# LED_Matrix-2.net
KiCad netlist of a schematic drawn in Altium Designer
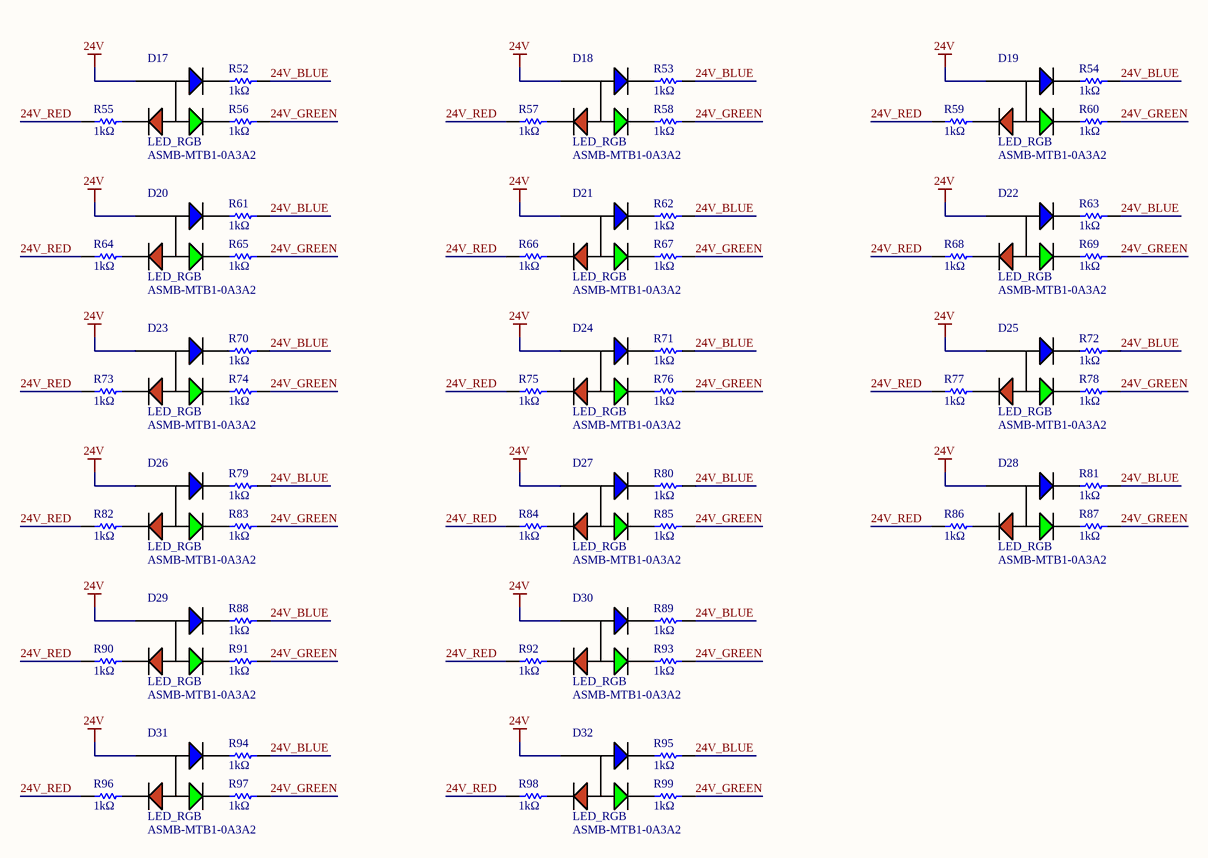
[diagram p0: LED Matrix-2.SchDoc]

(export (version "E")
  (design (tool "Eeschema 10.0.6"))
  (components
    (comp (ref "D17")
      (value "LED_RGB")
      (footprint "LED_RGB")
      (description "LED RGB DIFFUSED 4PLCC SMD")
      (fields (field (name "MANUFACTURER PART NUMBER 1") "ASMB-MTB1-0A3A2"))
      (libsource (lib "UWRT_Schematic_Library_2020") (part "LED_RGB"))
    )
    (comp (ref "D18")
      (value "LED_RGB")
      (footprint "LED_RGB")
      (description "LED RGB DIFFUSED 4PLCC SMD")
      (fields (field (name "MANUFACTURER PART NUMBER 1") "ASMB-MTB1-0A3A2"))
      (libsource (lib "UWRT_Schematic_Library_2020") (part "LED_RGB"))
    )
    (comp (ref "D19")
      (value "LED_RGB")
      (footprint "LED_RGB")
      (description "LED RGB DIFFUSED 4PLCC SMD")
      (fields (field (name "MANUFACTURER PART NUMBER 1") "ASMB-MTB1-0A3A2"))
      (libsource (lib "UWRT_Schematic_Library_2020") (part "LED_RGB"))
    )
    (comp (ref "D20")
      (value "LED_RGB")
      (footprint "LED_RGB")
      (description "LED RGB DIFFUSED 4PLCC SMD")
      (fields (field (name "MANUFACTURER PART NUMBER 1") "ASMB-MTB1-0A3A2"))
      (libsource (lib "UWRT_Schematic_Library_2020") (part "LED_RGB"))
    )
    (comp (ref "D21")
      (value "LED_RGB")
      (footprint "LED_RGB")
      (description "LED RGB DIFFUSED 4PLCC SMD")
      (fields (field (name "MANUFACTURER PART NUMBER 1") "ASMB-MTB1-0A3A2"))
      (libsource (lib "UWRT_Schematic_Library_2020") (part "LED_RGB"))
    )
    (comp (ref "D22")
      (value "LED_RGB")
      (footprint "LED_RGB")
      (description "LED RGB DIFFUSED 4PLCC SMD")
      (fields (field (name "MANUFACTURER PART NUMBER 1") "ASMB-MTB1-0A3A2"))
      (libsource (lib "UWRT_Schematic_Library_2020") (part "LED_RGB"))
    )
    (comp (ref "D23")
      (value "LED_RGB")
      (footprint "LED_RGB")
      (description "LED RGB DIFFUSED 4PLCC SMD")
      (fields (field (name "MANUFACTURER PART NUMBER 1") "ASMB-MTB1-0A3A2"))
      (libsource (lib "UWRT_Schematic_Library_2020") (part "LED_RGB"))
    )
    (comp (ref "D24")
      (value "LED_RGB")
      (footprint "LED_RGB")
      (description "LED RGB DIFFUSED 4PLCC SMD")
      (fields (field (name "MANUFACTURER PART NUMBER 1") "ASMB-MTB1-0A3A2"))
      (libsource (lib "UWRT_Schematic_Library_2020") (part "LED_RGB"))
    )
    (comp (ref "D25")
      (value "LED_RGB")
      (footprint "LED_RGB")
      (description "LED RGB DIFFUSED 4PLCC SMD")
      (fields (field (name "MANUFACTURER PART NUMBER 1") "ASMB-MTB1-0A3A2"))
      (libsource (lib "UWRT_Schematic_Library_2020") (part "LED_RGB"))
    )
    (comp (ref "D26")
      (value "LED_RGB")
      (footprint "LED_RGB")
      (description "LED RGB DIFFUSED 4PLCC SMD")
      (fields (field (name "MANUFACTURER PART NUMBER 1") "ASMB-MTB1-0A3A2"))
      (libsource (lib "UWRT_Schematic_Library_2020") (part "LED_RGB"))
    )
    (comp (ref "D27")
      (value "LED_RGB")
      (footprint "LED_RGB")
      (description "LED RGB DIFFUSED 4PLCC SMD")
      (fields (field (name "MANUFACTURER PART NUMBER 1") "ASMB-MTB1-0A3A2"))
      (libsource (lib "UWRT_Schematic_Library_2020") (part "LED_RGB"))
    )
    (comp (ref "D28")
      (value "LED_RGB")
      (footprint "LED_RGB")
      (description "LED RGB DIFFUSED 4PLCC SMD")
      (fields (field (name "MANUFACTURER PART NUMBER 1") "ASMB-MTB1-0A3A2"))
      (libsource (lib "UWRT_Schematic_Library_2020") (part "LED_RGB"))
    )
    (comp (ref "D29")
      (value "LED_RGB")
      (footprint "LED_RGB")
      (description "LED RGB DIFFUSED 4PLCC SMD")
      (fields (field (name "MANUFACTURER PART NUMBER 1") "ASMB-MTB1-0A3A2"))
      (libsource (lib "UWRT_Schematic_Library_2020") (part "LED_RGB"))
    )
    (comp (ref "D30")
      (value "LED_RGB")
      (footprint "LED_RGB")
      (description "LED RGB DIFFUSED 4PLCC SMD")
      (fields (field (name "MANUFACTURER PART NUMBER 1") "ASMB-MTB1-0A3A2"))
      (libsource (lib "UWRT_Schematic_Library_2020") (part "LED_RGB"))
    )
    (comp (ref "D31")
      (value "LED_RGB")
      (footprint "LED_RGB")
      (description "LED RGB DIFFUSED 4PLCC SMD")
      (fields (field (name "MANUFACTURER PART NUMBER 1") "ASMB-MTB1-0A3A2"))
      (libsource (lib "UWRT_Schematic_Library_2020") (part "LED_RGB"))
    )
    (comp (ref "D32")
      (value "LED_RGB")
      (footprint "LED_RGB")
      (description "LED RGB DIFFUSED 4PLCC SMD")
      (fields (field (name "MANUFACTURER PART NUMBER 1") "ASMB-MTB1-0A3A2"))
      (libsource (lib "UWRT_Schematic_Library_2020") (part "LED_RGB"))
    )
    (comp (ref "R52")
      (value "1kΩ")
      (footprint "RESC2012X60N")
      (description "RES SMD 1K OHM 1% 1/8W 0805")
      (fields (field (name "TOLERANCE") "1%"))
      (libsource (lib "UWRT_Schematic_Library_2020") (part "RES_1kΩ_0805"))
    )
    (comp (ref "R53")
      (value "1kΩ")
      (footprint "RESC2012X60N")
      (description "RES SMD 1K OHM 1% 1/8W 0805")
      (fields (field (name "TOLERANCE") "1%"))
      (libsource (lib "UWRT_Schematic_Library_2020") (part "RES_1kΩ_0805"))
    )
    (comp (ref "R54")
      (value "1kΩ")
      (footprint "RESC2012X60N")
      (description "RES SMD 1K OHM 1% 1/8W 0805")
      (fields (field (name "TOLERANCE") "1%"))
      (libsource (lib "UWRT_Schematic_Library_2020") (part "RES_1kΩ_0805"))
    )
    (comp (ref "R55")
      (value "1kΩ")
      (footprint "RESC2012X60N")
      (description "RES SMD 1K OHM 1% 1/8W 0805")
      (fields (field (name "TOLERANCE") "1%"))
      (libsource (lib "UWRT_Schematic_Library_2020") (part "RES_1kΩ_0805"))
    )
    (comp (ref "R56")
      (value "1kΩ")
      (footprint "RESC2012X60N")
      (description "RES SMD 1K OHM 1% 1/8W 0805")
      (fields (field (name "TOLERANCE") "1%"))
      (libsource (lib "UWRT_Schematic_Library_2020") (part "RES_1kΩ_0805"))
    )
    (comp (ref "R57")
      (value "1kΩ")
      (footprint "RESC2012X60N")
      (description "RES SMD 1K OHM 1% 1/8W 0805")
      (fields (field (name "TOLERANCE") "1%"))
      (libsource (lib "UWRT_Schematic_Library_2020") (part "RES_1kΩ_0805"))
    )
    (comp (ref "R58")
      (value "1kΩ")
      (footprint "RESC2012X60N")
      (description "RES SMD 1K OHM 1% 1/8W 0805")
      (fields (field (name "TOLERANCE") "1%"))
      (libsource (lib "UWRT_Schematic_Library_2020") (part "RES_1kΩ_0805"))
    )
    (comp (ref "R59")
      (value "1kΩ")
      (footprint "RESC2012X60N")
      (description "RES SMD 1K OHM 1% 1/8W 0805")
      (fields (field (name "TOLERANCE") "1%"))
      (libsource (lib "UWRT_Schematic_Library_2020") (part "RES_1kΩ_0805"))
    )
    (comp (ref "R60")
      (value "1kΩ")
      (footprint "RESC2012X60N")
      (description "RES SMD 1K OHM 1% 1/8W 0805")
      (fields (field (name "TOLERANCE") "1%"))
      (libsource (lib "UWRT_Schematic_Library_2020") (part "RES_1kΩ_0805"))
    )
    (comp (ref "R61")
      (value "1kΩ")
      (footprint "RESC2012X60N")
      (description "RES SMD 1K OHM 1% 1/8W 0805")
      (fields (field (name "TOLERANCE") "1%"))
      (libsource (lib "UWRT_Schematic_Library_2020") (part "RES_1kΩ_0805"))
    )
    (comp (ref "R62")
      (value "1kΩ")
      (footprint "RESC2012X60N")
      (description "RES SMD 1K OHM 1% 1/8W 0805")
      (fields (field (name "TOLERANCE") "1%"))
      (libsource (lib "UWRT_Schematic_Library_2020") (part "RES_1kΩ_0805"))
    )
    (comp (ref "R63")
      (value "1kΩ")
      (footprint "RESC2012X60N")
      (description "RES SMD 1K OHM 1% 1/8W 0805")
      (fields (field (name "TOLERANCE") "1%"))
      (libsource (lib "UWRT_Schematic_Library_2020") (part "RES_1kΩ_0805"))
    )
    (comp (ref "R64")
      (value "1kΩ")
      (footprint "RESC2012X60N")
      (description "RES SMD 1K OHM 1% 1/8W 0805")
      (fields (field (name "TOLERANCE") "1%"))
      (libsource (lib "UWRT_Schematic_Library_2020") (part "RES_1kΩ_0805"))
    )
    (comp (ref "R65")
      (value "1kΩ")
      (footprint "RESC2012X60N")
      (description "RES SMD 1K OHM 1% 1/8W 0805")
      (fields (field (name "TOLERANCE") "1%"))
      (libsource (lib "UWRT_Schematic_Library_2020") (part "RES_1kΩ_0805"))
    )
    (comp (ref "R66")
      (value "1kΩ")
      (footprint "RESC2012X60N")
      (description "RES SMD 1K OHM 1% 1/8W 0805")
      (fields (field (name "TOLERANCE") "1%"))
      (libsource (lib "UWRT_Schematic_Library_2020") (part "RES_1kΩ_0805"))
    )
    (comp (ref "R67")
      (value "1kΩ")
      (footprint "RESC2012X60N")
      (description "RES SMD 1K OHM 1% 1/8W 0805")
      (fields (field (name "TOLERANCE") "1%"))
      (libsource (lib "UWRT_Schematic_Library_2020") (part "RES_1kΩ_0805"))
    )
    (comp (ref "R68")
      (value "1kΩ")
      (footprint "RESC2012X60N")
      (description "RES SMD 1K OHM 1% 1/8W 0805")
      (fields (field (name "TOLERANCE") "1%"))
      (libsource (lib "UWRT_Schematic_Library_2020") (part "RES_1kΩ_0805"))
    )
    (comp (ref "R69")
      (value "1kΩ")
      (footprint "RESC2012X60N")
      (description "RES SMD 1K OHM 1% 1/8W 0805")
      (fields (field (name "TOLERANCE") "1%"))
      (libsource (lib "UWRT_Schematic_Library_2020") (part "RES_1kΩ_0805"))
    )
    (comp (ref "R70")
      (value "1kΩ")
      (footprint "RESC2012X60N")
      (description "RES SMD 1K OHM 1% 1/8W 0805")
      (fields (field (name "TOLERANCE") "1%"))
      (libsource (lib "UWRT_Schematic_Library_2020") (part "RES_1kΩ_0805"))
    )
    (comp (ref "R71")
      (value "1kΩ")
      (footprint "RESC2012X60N")
      (description "RES SMD 1K OHM 1% 1/8W 0805")
      (fields (field (name "TOLERANCE") "1%"))
      (libsource (lib "UWRT_Schematic_Library_2020") (part "RES_1kΩ_0805"))
    )
    (comp (ref "R72")
      (value "1kΩ")
      (footprint "RESC2012X60N")
      (description "RES SMD 1K OHM 1% 1/8W 0805")
      (fields (field (name "TOLERANCE") "1%"))
      (libsource (lib "UWRT_Schematic_Library_2020") (part "RES_1kΩ_0805"))
    )
    (comp (ref "R73")
      (value "1kΩ")
      (footprint "RESC2012X60N")
      (description "RES SMD 1K OHM 1% 1/8W 0805")
      (fields (field (name "TOLERANCE") "1%"))
      (libsource (lib "UWRT_Schematic_Library_2020") (part "RES_1kΩ_0805"))
    )
    (comp (ref "R74")
      (value "1kΩ")
      (footprint "RESC2012X60N")
      (description "RES SMD 1K OHM 1% 1/8W 0805")
      (fields (field (name "TOLERANCE") "1%"))
      (libsource (lib "UWRT_Schematic_Library_2020") (part "RES_1kΩ_0805"))
    )
    (comp (ref "R75")
      (value "1kΩ")
      (footprint "RESC2012X60N")
      (description "RES SMD 1K OHM 1% 1/8W 0805")
      (fields (field (name "TOLERANCE") "1%"))
      (libsource (lib "UWRT_Schematic_Library_2020") (part "RES_1kΩ_0805"))
    )
    (comp (ref "R76")
      (value "1kΩ")
      (footprint "RESC2012X60N")
      (description "RES SMD 1K OHM 1% 1/8W 0805")
      (fields (field (name "TOLERANCE") "1%"))
      (libsource (lib "UWRT_Schematic_Library_2020") (part "RES_1kΩ_0805"))
    )
    (comp (ref "R77")
      (value "1kΩ")
      (footprint "RESC2012X60N")
      (description "RES SMD 1K OHM 1% 1/8W 0805")
      (fields (field (name "TOLERANCE") "1%"))
      (libsource (lib "UWRT_Schematic_Library_2020") (part "RES_1kΩ_0805"))
    )
    (comp (ref "R78")
      (value "1kΩ")
      (footprint "RESC2012X60N")
      (description "RES SMD 1K OHM 1% 1/8W 0805")
      (fields (field (name "TOLERANCE") "1%"))
      (libsource (lib "UWRT_Schematic_Library_2020") (part "RES_1kΩ_0805"))
    )
    (comp (ref "R79")
      (value "1kΩ")
      (footprint "RESC2012X60N")
      (description "RES SMD 1K OHM 1% 1/8W 0805")
      (fields (field (name "TOLERANCE") "1%"))
      (libsource (lib "UWRT_Schematic_Library_2020") (part "RES_1kΩ_0805"))
    )
    (comp (ref "R80")
      (value "1kΩ")
      (footprint "RESC2012X60N")
      (description "RES SMD 1K OHM 1% 1/8W 0805")
      (fields (field (name "TOLERANCE") "1%"))
      (libsource (lib "UWRT_Schematic_Library_2020") (part "RES_1kΩ_0805"))
    )
    (comp (ref "R81")
      (value "1kΩ")
      (footprint "RESC2012X60N")
      (description "RES SMD 1K OHM 1% 1/8W 0805")
      (fields (field (name "TOLERANCE") "1%"))
      (libsource (lib "UWRT_Schematic_Library_2020") (part "RES_1kΩ_0805"))
    )
    (comp (ref "R82")
      (value "1kΩ")
      (footprint "RESC2012X60N")
      (description "RES SMD 1K OHM 1% 1/8W 0805")
      (fields (field (name "TOLERANCE") "1%"))
      (libsource (lib "UWRT_Schematic_Library_2020") (part "RES_1kΩ_0805"))
    )
    (comp (ref "R83")
      (value "1kΩ")
      (footprint "RESC2012X60N")
      (description "RES SMD 1K OHM 1% 1/8W 0805")
      (fields (field (name "TOLERANCE") "1%"))
      (libsource (lib "UWRT_Schematic_Library_2020") (part "RES_1kΩ_0805"))
    )
    (comp (ref "R84")
      (value "1kΩ")
      (footprint "RESC2012X60N")
      (description "RES SMD 1K OHM 1% 1/8W 0805")
      (fields (field (name "TOLERANCE") "1%"))
      (libsource (lib "UWRT_Schematic_Library_2020") (part "RES_1kΩ_0805"))
    )
    (comp (ref "R85")
      (value "1kΩ")
      (footprint "RESC2012X60N")
      (description "RES SMD 1K OHM 1% 1/8W 0805")
      (fields (field (name "TOLERANCE") "1%"))
      (libsource (lib "UWRT_Schematic_Library_2020") (part "RES_1kΩ_0805"))
    )
    (comp (ref "R86")
      (value "1kΩ")
      (footprint "RESC2012X60N")
      (description "RES SMD 1K OHM 1% 1/8W 0805")
      (fields (field (name "TOLERANCE") "1%"))
      (libsource (lib "UWRT_Schematic_Library_2020") (part "RES_1kΩ_0805"))
    )
    (comp (ref "R87")
      (value "1kΩ")
      (footprint "RESC2012X60N")
      (description "RES SMD 1K OHM 1% 1/8W 0805")
      (fields (field (name "TOLERANCE") "1%"))
      (libsource (lib "UWRT_Schematic_Library_2020") (part "RES_1kΩ_0805"))
    )
    (comp (ref "R88")
      (value "1kΩ")
      (footprint "RESC2012X60N")
      (description "RES SMD 1K OHM 1% 1/8W 0805")
      (fields (field (name "TOLERANCE") "1%"))
      (libsource (lib "UWRT_Schematic_Library_2020") (part "RES_1kΩ_0805"))
    )
    (comp (ref "R89")
      (value "1kΩ")
      (footprint "RESC2012X60N")
      (description "RES SMD 1K OHM 1% 1/8W 0805")
      (fields (field (name "TOLERANCE") "1%"))
      (libsource (lib "UWRT_Schematic_Library_2020") (part "RES_1kΩ_0805"))
    )
    (comp (ref "R90")
      (value "1kΩ")
      (footprint "RESC2012X60N")
      (description "RES SMD 1K OHM 1% 1/8W 0805")
      (fields (field (name "TOLERANCE") "1%"))
      (libsource (lib "UWRT_Schematic_Library_2020") (part "RES_1kΩ_0805"))
    )
    (comp (ref "R91")
      (value "1kΩ")
      (footprint "RESC2012X60N")
      (description "RES SMD 1K OHM 1% 1/8W 0805")
      (fields (field (name "TOLERANCE") "1%"))
      (libsource (lib "UWRT_Schematic_Library_2020") (part "RES_1kΩ_0805"))
    )
    (comp (ref "R92")
      (value "1kΩ")
      (footprint "RESC2012X60N")
      (description "RES SMD 1K OHM 1% 1/8W 0805")
      (fields (field (name "TOLERANCE") "1%"))
      (libsource (lib "UWRT_Schematic_Library_2020") (part "RES_1kΩ_0805"))
    )
    (comp (ref "R93")
      (value "1kΩ")
      (footprint "RESC2012X60N")
      (description "RES SMD 1K OHM 1% 1/8W 0805")
      (fields (field (name "TOLERANCE") "1%"))
      (libsource (lib "UWRT_Schematic_Library_2020") (part "RES_1kΩ_0805"))
    )
    (comp (ref "R94")
      (value "1kΩ")
      (footprint "RESC2012X60N")
      (description "RES SMD 1K OHM 1% 1/8W 0805")
      (fields (field (name "TOLERANCE") "1%"))
      (libsource (lib "UWRT_Schematic_Library_2020") (part "RES_1kΩ_0805"))
    )
    (comp (ref "R95")
      (value "1kΩ")
      (footprint "RESC2012X60N")
      (description "RES SMD 1K OHM 1% 1/8W 0805")
      (fields (field (name "TOLERANCE") "1%"))
      (libsource (lib "UWRT_Schematic_Library_2020") (part "RES_1kΩ_0805"))
    )
    (comp (ref "R96")
      (value "1kΩ")
      (footprint "RESC2012X60N")
      (description "RES SMD 1K OHM 1% 1/8W 0805")
      (fields (field (name "TOLERANCE") "1%"))
      (libsource (lib "UWRT_Schematic_Library_2020") (part "RES_1kΩ_0805"))
    )
    (comp (ref "R97")
      (value "1kΩ")
      (footprint "RESC2012X60N")
      (description "RES SMD 1K OHM 1% 1/8W 0805")
      (fields (field (name "TOLERANCE") "1%"))
      (libsource (lib "UWRT_Schematic_Library_2020") (part "RES_1kΩ_0805"))
    )
    (comp (ref "R98")
      (value "1kΩ")
      (footprint "RESC2012X60N")
      (description "RES SMD 1K OHM 1% 1/8W 0805")
      (fields (field (name "TOLERANCE") "1%"))
      (libsource (lib "UWRT_Schematic_Library_2020") (part "RES_1kΩ_0805"))
    )
    (comp (ref "R99")
      (value "1kΩ")
      (footprint "RESC2012X60N")
      (description "RES SMD 1K OHM 1% 1/8W 0805")
      (fields (field (name "TOLERANCE") "1%"))
      (libsource (lib "UWRT_Schematic_Library_2020") (part "RES_1kΩ_0805"))
    )
  )
  (nets
    (net (code "1") (name "/24V_BLUE") (class "Default")
      (node (ref "R52") (pin "2") (pinfunction "2_2") (pintype "passive"))
      (node (ref "R53") (pin "2") (pinfunction "2_2") (pintype "passive"))
      (node (ref "R54") (pin "2") (pinfunction "2_2") (pintype "passive"))
      (node (ref "R61") (pin "2") (pinfunction "2_2") (pintype "passive"))
      (node (ref "R62") (pin "2") (pinfunction "2_2") (pintype "passive"))
      (node (ref "R63") (pin "2") (pinfunction "2_2") (pintype "passive"))
      (node (ref "R70") (pin "2") (pinfunction "2_2") (pintype "passive"))
      (node (ref "R71") (pin "2") (pinfunction "2_2") (pintype "passive"))
      (node (ref "R72") (pin "2") (pinfunction "2_2") (pintype "passive"))
      (node (ref "R79") (pin "2") (pinfunction "2_2") (pintype "passive"))
      (node (ref "R80") (pin "2") (pinfunction "2_2") (pintype "passive"))
      (node (ref "R81") (pin "2") (pinfunction "2_2") (pintype "passive"))
      (node (ref "R88") (pin "2") (pinfunction "2_2") (pintype "passive"))
      (node (ref "R89") (pin "2") (pinfunction "2_2") (pintype "passive"))
      (node (ref "R94") (pin "2") (pinfunction "2_2") (pintype "passive"))
      (node (ref "R95") (pin "2") (pinfunction "2_2") (pintype "passive"))
    )
    (net (code "2") (name "/24V_GREEN") (class "Default")
      (node (ref "R56") (pin "2") (pinfunction "2_2") (pintype "passive"))
      (node (ref "R58") (pin "2") (pinfunction "2_2") (pintype "passive"))
      (node (ref "R60") (pin "2") (pinfunction "2_2") (pintype "passive"))
      (node (ref "R65") (pin "2") (pinfunction "2_2") (pintype "passive"))
      (node (ref "R67") (pin "2") (pinfunction "2_2") (pintype "passive"))
      (node (ref "R69") (pin "2") (pinfunction "2_2") (pintype "passive"))
      (node (ref "R74") (pin "2") (pinfunction "2_2") (pintype "passive"))
      (node (ref "R76") (pin "2") (pinfunction "2_2") (pintype "passive"))
      (node (ref "R78") (pin "2") (pinfunction "2_2") (pintype "passive"))
      (node (ref "R83") (pin "2") (pinfunction "2_2") (pintype "passive"))
      (node (ref "R85") (pin "2") (pinfunction "2_2") (pintype "passive"))
      (node (ref "R87") (pin "2") (pinfunction "2_2") (pintype "passive"))
      (node (ref "R91") (pin "2") (pinfunction "2_2") (pintype "passive"))
      (node (ref "R93") (pin "2") (pinfunction "2_2") (pintype "passive"))
      (node (ref "R97") (pin "2") (pinfunction "2_2") (pintype "passive"))
      (node (ref "R99") (pin "2") (pinfunction "2_2") (pintype "passive"))
    )
    (net (code "3") (name "/24V_RED") (class "Default")
      (node (ref "R55") (pin "1") (pinfunction "1_1") (pintype "passive"))
      (node (ref "R57") (pin "1") (pinfunction "1_1") (pintype "passive"))
      (node (ref "R59") (pin "1") (pinfunction "1_1") (pintype "passive"))
      (node (ref "R64") (pin "1") (pinfunction "1_1") (pintype "passive"))
      (node (ref "R66") (pin "1") (pinfunction "1_1") (pintype "passive"))
      (node (ref "R68") (pin "1") (pinfunction "1_1") (pintype "passive"))
      (node (ref "R73") (pin "1") (pinfunction "1_1") (pintype "passive"))
      (node (ref "R75") (pin "1") (pinfunction "1_1") (pintype "passive"))
      (node (ref "R77") (pin "1") (pinfunction "1_1") (pintype "passive"))
      (node (ref "R82") (pin "1") (pinfunction "1_1") (pintype "passive"))
      (node (ref "R84") (pin "1") (pinfunction "1_1") (pintype "passive"))
      (node (ref "R86") (pin "1") (pinfunction "1_1") (pintype "passive"))
      (node (ref "R90") (pin "1") (pinfunction "1_1") (pintype "passive"))
      (node (ref "R92") (pin "1") (pinfunction "1_1") (pintype "passive"))
      (node (ref "R96") (pin "1") (pinfunction "1_1") (pintype "passive"))
      (node (ref "R98") (pin "1") (pinfunction "1_1") (pintype "passive"))
    )
    (net (code "4") (name "24V") (class "Default")
      (node (ref "D17") (pin "4") (pinfunction "COMMON_ANODE_4") (pintype "passive"))
      (node (ref "D18") (pin "4") (pinfunction "COMMON_ANODE_4") (pintype "passive"))
      (node (ref "D19") (pin "4") (pinfunction "COMMON_ANODE_4") (pintype "passive"))
      (node (ref "D20") (pin "4") (pinfunction "COMMON_ANODE_4") (pintype "passive"))
      (node (ref "D21") (pin "4") (pinfunction "COMMON_ANODE_4") (pintype "passive"))
      (node (ref "D22") (pin "4") (pinfunction "COMMON_ANODE_4") (pintype "passive"))
      (node (ref "D23") (pin "4") (pinfunction "COMMON_ANODE_4") (pintype "passive"))
      (node (ref "D24") (pin "4") (pinfunction "COMMON_ANODE_4") (pintype "passive"))
      (node (ref "D25") (pin "4") (pinfunction "COMMON_ANODE_4") (pintype "passive"))
      (node (ref "D26") (pin "4") (pinfunction "COMMON_ANODE_4") (pintype "passive"))
      (node (ref "D27") (pin "4") (pinfunction "COMMON_ANODE_4") (pintype "passive"))
      (node (ref "D28") (pin "4") (pinfunction "COMMON_ANODE_4") (pintype "passive"))
      (node (ref "D29") (pin "4") (pinfunction "COMMON_ANODE_4") (pintype "passive"))
      (node (ref "D30") (pin "4") (pinfunction "COMMON_ANODE_4") (pintype "passive"))
      (node (ref "D31") (pin "4") (pinfunction "COMMON_ANODE_4") (pintype "passive"))
      (node (ref "D32") (pin "4") (pinfunction "COMMON_ANODE_4") (pintype "passive"))
    )
    (net (code "5") (name "Net-(D17-CATHODE_(BLUE))") (class "Default")
      (node (ref "D17") (pin "3") (pinfunction "CATHODE_(BLUE)_3") (pintype "passive"))
      (node (ref "R52") (pin "1") (pinfunction "1_1") (pintype "passive"))
    )
    (net (code "6") (name "Net-(D17-CATHODE_(GREEN))") (class "Default")
      (node (ref "D17") (pin "2") (pinfunction "CATHODE_(GREEN)_2") (pintype "passive"))
      (node (ref "R56") (pin "1") (pinfunction "1_1") (pintype "passive"))
    )
    (net (code "7") (name "Net-(D17-CATHODE_(RED))") (class "Default")
      (node (ref "D17") (pin "1") (pinfunction "CATHODE_(RED)_1") (pintype "passive"))
      (node (ref "R55") (pin "2") (pinfunction "2_2") (pintype "passive"))
    )
    (net (code "8") (name "Net-(D18-CATHODE_(BLUE))") (class "Default")
      (node (ref "D18") (pin "3") (pinfunction "CATHODE_(BLUE)_3") (pintype "passive"))
      (node (ref "R53") (pin "1") (pinfunction "1_1") (pintype "passive"))
    )
    (net (code "9") (name "Net-(D18-CATHODE_(GREEN))") (class "Default")
      (node (ref "D18") (pin "2") (pinfunction "CATHODE_(GREEN)_2") (pintype "passive"))
      (node (ref "R58") (pin "1") (pinfunction "1_1") (pintype "passive"))
    )
    (net (code "10") (name "Net-(D18-CATHODE_(RED))") (class "Default")
      (node (ref "D18") (pin "1") (pinfunction "CATHODE_(RED)_1") (pintype "passive"))
      (node (ref "R57") (pin "2") (pinfunction "2_2") (pintype "passive"))
    )
    (net (code "11") (name "Net-(D19-CATHODE_(BLUE))") (class "Default")
      (node (ref "D19") (pin "3") (pinfunction "CATHODE_(BLUE)_3") (pintype "passive"))
      (node (ref "R54") (pin "1") (pinfunction "1_1") (pintype "passive"))
    )
    (net (code "12") (name "Net-(D19-CATHODE_(GREEN))") (class "Default")
      (node (ref "D19") (pin "2") (pinfunction "CATHODE_(GREEN)_2") (pintype "passive"))
      (node (ref "R60") (pin "1") (pinfunction "1_1") (pintype "passive"))
    )
    (net (code "13") (name "Net-(D19-CATHODE_(RED))") (class "Default")
      (node (ref "D19") (pin "1") (pinfunction "CATHODE_(RED)_1") (pintype "passive"))
      (node (ref "R59") (pin "2") (pinfunction "2_2") (pintype "passive"))
    )
    (net (code "14") (name "Net-(D20-CATHODE_(BLUE))") (class "Default")
      (node (ref "D20") (pin "3") (pinfunction "CATHODE_(BLUE)_3") (pintype "passive"))
      (node (ref "R61") (pin "1") (pinfunction "1_1") (pintype "passive"))
    )
    (net (code "15") (name "Net-(D20-CATHODE_(GREEN))") (class "Default")
      (node (ref "D20") (pin "2") (pinfunction "CATHODE_(GREEN)_2") (pintype "passive"))
      (node (ref "R65") (pin "1") (pinfunction "1_1") (pintype "passive"))
    )
    (net (code "16") (name "Net-(D20-CATHODE_(RED))") (class "Default")
      (node (ref "D20") (pin "1") (pinfunction "CATHODE_(RED)_1") (pintype "passive"))
      (node (ref "R64") (pin "2") (pinfunction "2_2") (pintype "passive"))
    )
    (net (code "17") (name "Net-(D21-CATHODE_(BLUE))") (class "Default")
      (node (ref "D21") (pin "3") (pinfunction "CATHODE_(BLUE)_3") (pintype "passive"))
      (node (ref "R62") (pin "1") (pinfunction "1_1") (pintype "passive"))
    )
    (net (code "18") (name "Net-(D21-CATHODE_(GREEN))") (class "Default")
      (node (ref "D21") (pin "2") (pinfunction "CATHODE_(GREEN)_2") (pintype "passive"))
      (node (ref "R67") (pin "1") (pinfunction "1_1") (pintype "passive"))
    )
    (net (code "19") (name "Net-(D21-CATHODE_(RED))") (class "Default")
      (node (ref "D21") (pin "1") (pinfunction "CATHODE_(RED)_1") (pintype "passive"))
      (node (ref "R66") (pin "2") (pinfunction "2_2") (pintype "passive"))
    )
    (net (code "20") (name "Net-(D22-CATHODE_(BLUE))") (class "Default")
      (node (ref "D22") (pin "3") (pinfunction "CATHODE_(BLUE)_3") (pintype "passive"))
      (node (ref "R63") (pin "1") (pinfunction "1_1") (pintype "passive"))
    )
    (net (code "21") (name "Net-(D22-CATHODE_(GREEN))") (class "Default")
      (node (ref "D22") (pin "2") (pinfunction "CATHODE_(GREEN)_2") (pintype "passive"))
      (node (ref "R69") (pin "1") (pinfunction "1_1") (pintype "passive"))
    )
    (net (code "22") (name "Net-(D22-CATHODE_(RED))") (class "Default")
      (node (ref "D22") (pin "1") (pinfunction "CATHODE_(RED)_1") (pintype "passive"))
      (node (ref "R68") (pin "2") (pinfunction "2_2") (pintype "passive"))
    )
    (net (code "23") (name "Net-(D23-CATHODE_(BLUE))") (class "Default")
      (node (ref "D23") (pin "3") (pinfunction "CATHODE_(BLUE)_3") (pintype "passive"))
      (node (ref "R70") (pin "1") (pinfunction "1_1") (pintype "passive"))
    )
    (net (code "24") (name "Net-(D23-CATHODE_(GREEN))") (class "Default")
      (node (ref "D23") (pin "2") (pinfunction "CATHODE_(GREEN)_2") (pintype "passive"))
      (node (ref "R74") (pin "1") (pinfunction "1_1") (pintype "passive"))
    )
    (net (code "25") (name "Net-(D23-CATHODE_(RED))") (class "Default")
      (node (ref "D23") (pin "1") (pinfunction "CATHODE_(RED)_1") (pintype "passive"))
      (node (ref "R73") (pin "2") (pinfunction "2_2") (pintype "passive"))
    )
    (net (code "26") (name "Net-(D24-CATHODE_(BLUE))") (class "Default")
      (node (ref "D24") (pin "3") (pinfunction "CATHODE_(BLUE)_3") (pintype "passive"))
      (node (ref "R71") (pin "1") (pinfunction "1_1") (pintype "passive"))
    )
    (net (code "27") (name "Net-(D24-CATHODE_(GREEN))") (class "Default")
      (node (ref "D24") (pin "2") (pinfunction "CATHODE_(GREEN)_2") (pintype "passive"))
      (node (ref "R76") (pin "1") (pinfunction "1_1") (pintype "passive"))
    )
    (net (code "28") (name "Net-(D24-CATHODE_(RED))") (class "Default")
      (node (ref "D24") (pin "1") (pinfunction "CATHODE_(RED)_1") (pintype "passive"))
      (node (ref "R75") (pin "2") (pinfunction "2_2") (pintype "passive"))
    )
    (net (code "29") (name "Net-(D25-CATHODE_(BLUE))") (class "Default")
      (node (ref "D25") (pin "3") (pinfunction "CATHODE_(BLUE)_3") (pintype "passive"))
      (node (ref "R72") (pin "1") (pinfunction "1_1") (pintype "passive"))
    )
    (net (code "30") (name "Net-(D25-CATHODE_(GREEN))") (class "Default")
      (node (ref "D25") (pin "2") (pinfunction "CATHODE_(GREEN)_2") (pintype "passive"))
      (node (ref "R78") (pin "1") (pinfunction "1_1") (pintype "passive"))
    )
    (net (code "31") (name "Net-(D25-CATHODE_(RED))") (class "Default")
      (node (ref "D25") (pin "1") (pinfunction "CATHODE_(RED)_1") (pintype "passive"))
      (node (ref "R77") (pin "2") (pinfunction "2_2") (pintype "passive"))
    )
    (net (code "32") (name "Net-(D26-CATHODE_(BLUE))") (class "Default")
      (node (ref "D26") (pin "3") (pinfunction "CATHODE_(BLUE)_3") (pintype "passive"))
      (node (ref "R79") (pin "1") (pinfunction "1_1") (pintype "passive"))
    )
    (net (code "33") (name "Net-(D26-CATHODE_(GREEN))") (class "Default")
      (node (ref "D26") (pin "2") (pinfunction "CATHODE_(GREEN)_2") (pintype "passive"))
      (node (ref "R83") (pin "1") (pinfunction "1_1") (pintype "passive"))
    )
    (net (code "34") (name "Net-(D26-CATHODE_(RED))") (class "Default")
      (node (ref "D26") (pin "1") (pinfunction "CATHODE_(RED)_1") (pintype "passive"))
      (node (ref "R82") (pin "2") (pinfunction "2_2") (pintype "passive"))
    )
    (net (code "35") (name "Net-(D27-CATHODE_(BLUE))") (class "Default")
      (node (ref "D27") (pin "3") (pinfunction "CATHODE_(BLUE)_3") (pintype "passive"))
      (node (ref "R80") (pin "1") (pinfunction "1_1") (pintype "passive"))
    )
    (net (code "36") (name "Net-(D27-CATHODE_(GREEN))") (class "Default")
      (node (ref "D27") (pin "2") (pinfunction "CATHODE_(GREEN)_2") (pintype "passive"))
      (node (ref "R85") (pin "1") (pinfunction "1_1") (pintype "passive"))
    )
    (net (code "37") (name "Net-(D27-CATHODE_(RED))") (class "Default")
      (node (ref "D27") (pin "1") (pinfunction "CATHODE_(RED)_1") (pintype "passive"))
      (node (ref "R84") (pin "2") (pinfunction "2_2") (pintype "passive"))
    )
    (net (code "38") (name "Net-(D28-CATHODE_(BLUE))") (class "Default")
      (node (ref "D28") (pin "3") (pinfunction "CATHODE_(BLUE)_3") (pintype "passive"))
      (node (ref "R81") (pin "1") (pinfunction "1_1") (pintype "passive"))
    )
    (net (code "39") (name "Net-(D28-CATHODE_(GREEN))") (class "Default")
      (node (ref "D28") (pin "2") (pinfunction "CATHODE_(GREEN)_2") (pintype "passive"))
      (node (ref "R87") (pin "1") (pinfunction "1_1") (pintype "passive"))
    )
    (net (code "40") (name "Net-(D28-CATHODE_(RED))") (class "Default")
      (node (ref "D28") (pin "1") (pinfunction "CATHODE_(RED)_1") (pintype "passive"))
      (node (ref "R86") (pin "2") (pinfunction "2_2") (pintype "passive"))
    )
    (net (code "41") (name "Net-(D29-CATHODE_(BLUE))") (class "Default")
      (node (ref "D29") (pin "3") (pinfunction "CATHODE_(BLUE)_3") (pintype "passive"))
      (node (ref "R88") (pin "1") (pinfunction "1_1") (pintype "passive"))
    )
    (net (code "42") (name "Net-(D29-CATHODE_(GREEN))") (class "Default")
      (node (ref "D29") (pin "2") (pinfunction "CATHODE_(GREEN)_2") (pintype "passive"))
      (node (ref "R91") (pin "1") (pinfunction "1_1") (pintype "passive"))
    )
    (net (code "43") (name "Net-(D29-CATHODE_(RED))") (class "Default")
      (node (ref "D29") (pin "1") (pinfunction "CATHODE_(RED)_1") (pintype "passive"))
      (node (ref "R90") (pin "2") (pinfunction "2_2") (pintype "passive"))
    )
    (net (code "44") (name "Net-(D30-CATHODE_(BLUE))") (class "Default")
      (node (ref "D30") (pin "3") (pinfunction "CATHODE_(BLUE)_3") (pintype "passive"))
      (node (ref "R89") (pin "1") (pinfunction "1_1") (pintype "passive"))
    )
    (net (code "45") (name "Net-(D30-CATHODE_(GREEN))") (class "Default")
      (node (ref "D30") (pin "2") (pinfunction "CATHODE_(GREEN)_2") (pintype "passive"))
      (node (ref "R93") (pin "1") (pinfunction "1_1") (pintype "passive"))
    )
    (net (code "46") (name "Net-(D30-CATHODE_(RED))") (class "Default")
      (node (ref "D30") (pin "1") (pinfunction "CATHODE_(RED)_1") (pintype "passive"))
      (node (ref "R92") (pin "2") (pinfunction "2_2") (pintype "passive"))
    )
    (net (code "47") (name "Net-(D31-CATHODE_(BLUE))") (class "Default")
      (node (ref "D31") (pin "3") (pinfunction "CATHODE_(BLUE)_3") (pintype "passive"))
      (node (ref "R94") (pin "1") (pinfunction "1_1") (pintype "passive"))
    )
    (net (code "48") (name "Net-(D31-CATHODE_(GREEN))") (class "Default")
      (node (ref "D31") (pin "2") (pinfunction "CATHODE_(GREEN)_2") (pintype "passive"))
      (node (ref "R97") (pin "1") (pinfunction "1_1") (pintype "passive"))
    )
    (net (code "49") (name "Net-(D31-CATHODE_(RED))") (class "Default")
      (node (ref "D31") (pin "1") (pinfunction "CATHODE_(RED)_1") (pintype "passive"))
      (node (ref "R96") (pin "2") (pinfunction "2_2") (pintype "passive"))
    )
    (net (code "50") (name "Net-(D32-CATHODE_(BLUE))") (class "Default")
      (node (ref "D32") (pin "3") (pinfunction "CATHODE_(BLUE)_3") (pintype "passive"))
      (node (ref "R95") (pin "1") (pinfunction "1_1") (pintype "passive"))
    )
    (net (code "51") (name "Net-(D32-CATHODE_(GREEN))") (class "Default")
      (node (ref "D32") (pin "2") (pinfunction "CATHODE_(GREEN)_2") (pintype "passive"))
      (node (ref "R99") (pin "1") (pinfunction "1_1") (pintype "passive"))
    )
    (net (code "52") (name "Net-(D32-CATHODE_(RED))") (class "Default")
      (node (ref "D32") (pin "1") (pinfunction "CATHODE_(RED)_1") (pintype "passive"))
      (node (ref "R98") (pin "2") (pinfunction "2_2") (pintype "passive"))
    )
  )
)
